# KEY.net
KiCad netlist of a schematic drawn in Altium Designer
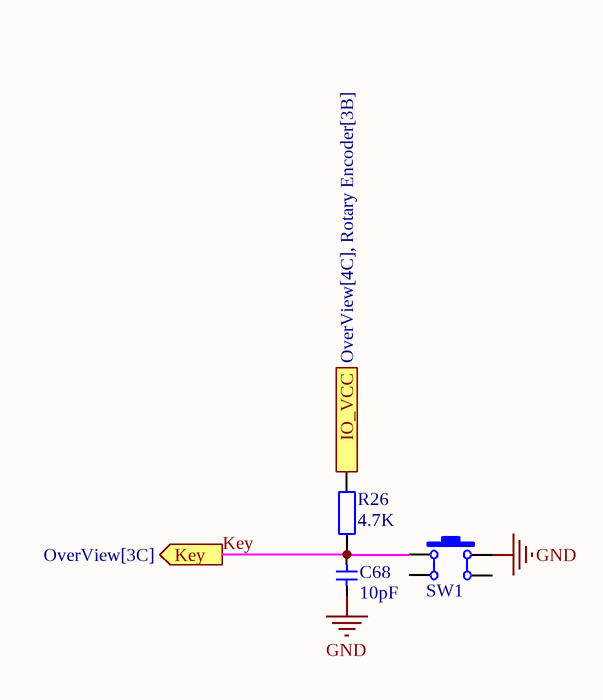
[diagram p0: KEY.SchDoc]

(export (version "E")
  (design (tool "Eeschema 10.0.6"))
  (components
    (comp (ref "C68")
      (value "10pF")
      (footprint "0402_CAP")
      (description "Capacitor")
      (libsource (lib "MyLib") (part "C"))
    )
    (comp (ref "R26")
      (value "4.7K")
      (footprint "0402_RES")
      (description "贴片电阻")
      (libsource (lib "0.1 - 电阻-电容-电感-保险丝-晶振-晶体-磁珠-电位器-法拉电容-馈通电容") (part "R"))
    )
    (comp (ref "SW1")
      (value "TD-1187SA-250")
      (footprint "SW-SMD-3.5*3.0_4P")
      (description "小乌龟-侧按4脚开关 带定位柱")
      (libsource (lib "0.5 - 按键_开关_蜂鸣器_电池_测试点_Mark点_铜柱") (part "TD-1187SA-250"))
    )
  )
  (nets
    (net (code "1") (name "/IO_VCC") (class "Default")
      (node (ref "R26") (pin "2") (pinfunction "2_2") (pintype "passive"))
    )
    (net (code "2") (name "/Key") (class "Default")
      (node (ref "C68") (pin "2") (pinfunction "2_2") (pintype "passive"))
      (node (ref "R26") (pin "1") (pinfunction "1_1") (pintype "passive"))
      (node (ref "SW1") (pin "1") (pinfunction "1_1") (pintype "passive"))
    )
    (net (code "3") (name "GND") (class "Default")
      (node (ref "C68") (pin "1") (pinfunction "1_1") (pintype "passive"))
      (node (ref "SW1") (pin "2") (pinfunction "2_2") (pintype "passive"))
    )
    (net (code "4") (name "unconnected-(SW1-Pad3)") (class "Default")
      (node (ref "SW1") (pin "3") (pinfunction "3_3") (pintype "passive"))
    )
    (net (code "5") (name "unconnected-(SW1-Pad4)") (class "Default")
      (node (ref "SW1") (pin "4") (pinfunction "4_4") (pintype "passive"))
    )
  )
)
